# NRF24L01_Module_AnTenna.net
KiCad netlist of a schematic drawn in EAGLE
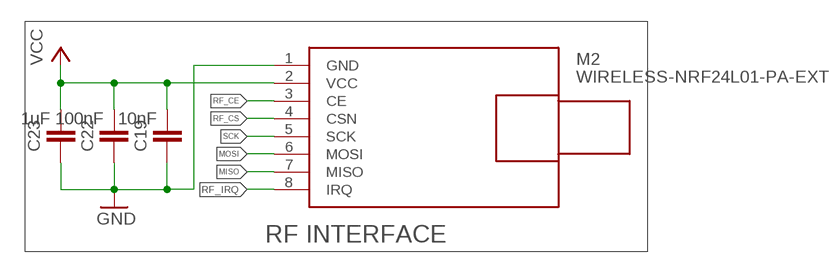
[diagram p0: schematic, sheet 1]

(export (version "E")
  (design (tool "Eeschema 10.0.6"))
  (components
    (comp (ref "C19")
      (value "10nF")
      (footprint "eagle-import:C050-024X044")
      (libsource (lib "eagle-import") (part "C-EU050-024X044"))
    )
    (comp (ref "C22")
      (value "100nF")
      (footprint "eagle-import:C050-024X044")
      (libsource (lib "eagle-import") (part "C-EU050-024X044"))
    )
    (comp (ref "C23")
      (value "1uF")
      (footprint "eagle-import:C050-024X044")
      (libsource (lib "eagle-import") (part "C-EU050-024X044"))
    )
    (comp (ref "M2")
      (value "WIRELESS-NRF24L01-PA-EXT")
      (footprint "eagle-import:WIRELESS-NRF24L01-PA-EXT")
      (libsource (lib "eagle-import") (part "WIRELESS-NRF24L01-PA-EXT"))
    )
  )
  (nets
    (net (code "1") (name "GND") (class "Default")
      (node (ref "C19") (pin "1") (pinfunction "1_1") (pintype "passive"))
      (node (ref "C22") (pin "1") (pinfunction "1_1") (pintype "passive"))
      (node (ref "C23") (pin "1") (pinfunction "1_1") (pintype "passive"))
      (node (ref "M2") (pin "1") (pinfunction "GND_1") (pintype "power_in"))
    )
    (net (code "2") (name "MISO") (class "Default")
      (node (ref "M2") (pin "7") (pinfunction "MISO_7") (pintype "bidirectional"))
    )
    (net (code "3") (name "MOSI") (class "Default")
      (node (ref "M2") (pin "6") (pinfunction "MOSI_6") (pintype "bidirectional"))
    )
    (net (code "4") (name "RF_CE") (class "Default")
      (node (ref "M2") (pin "3") (pinfunction "CE_3") (pintype "bidirectional"))
    )
    (net (code "5") (name "RF_CS") (class "Default")
      (node (ref "M2") (pin "4") (pinfunction "CSN_4") (pintype "bidirectional"))
    )
    (net (code "6") (name "RF_IRQ") (class "Default")
      (node (ref "M2") (pin "8") (pinfunction "IRQ_8") (pintype "bidirectional"))
    )
    (net (code "7") (name "SCK") (class "Default")
      (node (ref "M2") (pin "5") (pinfunction "SCK_5") (pintype "bidirectional"))
    )
    (net (code "8") (name "VCC") (class "Default")
      (node (ref "C19") (pin "2") (pinfunction "2_2") (pintype "passive"))
      (node (ref "C22") (pin "2") (pinfunction "2_2") (pintype "passive"))
      (node (ref "C23") (pin "2") (pinfunction "2_2") (pintype "passive"))
      (node (ref "M2") (pin "2") (pinfunction "VCC_2") (pintype "power_in"))
    )
  )
)
